# Meow.net
KiCad netlist of a schematic drawn in Altium Designer
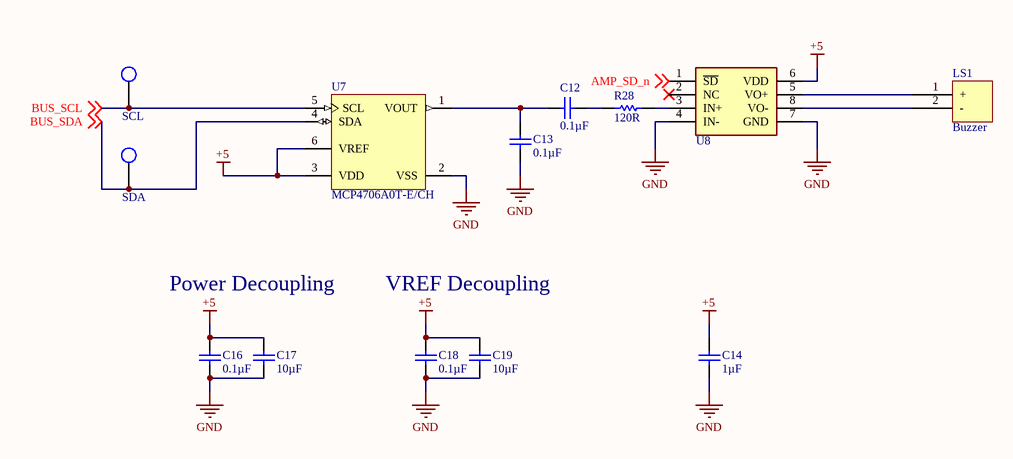
[diagram p0: Meow.SchDoc]

(export (version "E")
  (design (tool "Eeschema 10.0.6"))
  (components
    (comp (ref "C12")
      (value "Capacitor 0805")
      (footprint "Cap 0805")
      (description "Standard Capacitor")
      (fields (field (name "MANUFACTURER") "AVX") (field (name "CAPACITANCE") "0.1µF"))
      (libsource (lib "Standard Cap") (part "Capacitor 0805"))
    )
    (comp (ref "C13")
      (value "Capacitor 0805")
      (footprint "Cap 0805")
      (description "Standard Capacitor")
      (fields (field (name "MANUFACTURER") "AVX") (field (name "CAPACITANCE") "0.1µF"))
      (libsource (lib "Standard Cap") (part "Capacitor 0805"))
    )
    (comp (ref "C14")
      (value "Capacitor 0805")
      (footprint "Cap 0805")
      (description "Standard Capacitor")
      (fields (field (name "MANUFACTURER") "AVX") (field (name "CAPACITANCE") "1µF"))
      (libsource (lib "Standard Cap") (part "Capacitor 0805"))
    )
    (comp (ref "C16")
      (value "Capacitor 0805")
      (footprint "Cap 0805")
      (description "Standard Capacitor")
      (fields (field (name "MANUFACTURER") "AVX") (field (name "CAPACITANCE") "0.1µF"))
      (libsource (lib "Standard Cap") (part "Capacitor 0805"))
    )
    (comp (ref "C17")
      (value "Capacitor 0805")
      (footprint "Cap 0805")
      (description "Standard Capacitor")
      (fields (field (name "MANUFACTURER") "AVX") (field (name "CAPACITANCE") "10µF"))
      (libsource (lib "Standard Cap") (part "Capacitor 0805"))
    )
    (comp (ref "C18")
      (value "Capacitor 0805")
      (footprint "Cap 0805")
      (description "Standard Capacitor")
      (fields (field (name "MANUFACTURER") "AVX") (field (name "CAPACITANCE") "0.1µF"))
      (libsource (lib "Standard Cap") (part "Capacitor 0805"))
    )
    (comp (ref "C19")
      (value "Capacitor 0805")
      (footprint "Cap 0805")
      (description "Standard Capacitor")
      (fields (field (name "MANUFACTURER") "AVX") (field (name "CAPACITANCE") "10µF"))
      (libsource (lib "Standard Cap") (part "Capacitor 0805"))
    )
    (comp (ref "LS1")
      (value "Buzzer")
      (footprint "Buzzer")
      (description "PK-21N30PQ")
      (libsource (lib "Husky Robotics Standard Library 2019-2020") (part "Buzzer"))
    )
    (comp (ref "R28")
      (value "120R")
      (footprint "RESC0805(2012)_N")
      (description "Generic 0805 Resistor")
      (fields (field (name "TOLERANCE") "5 %") (field (name "POWER") "0.125 W"))
      (libsource (lib "Husky Robotics Standard Library 2019-2020") (part "Resistor 0805"))
    )
    (comp (ref "SCL")
      (value "Test Point")
      (footprint "Test Point Through-hole")
      (libsource (lib "Husky Robotics Standard Library 2019-2020") (part "Test Point"))
    )
    (comp (ref "SDA")
      (value "Test Point")
      (footprint "Test Point Through-hole")
      (libsource (lib "Husky Robotics Standard Library 2019-2020") (part "Test Point"))
    )
    (comp (ref "U7")
      (value "MCP4706A0T-E/CH")
      (footprint "SOT-23-CH6_M")
      (libsource (lib "Altium Content Vault") (part "CON-DAC-MCP4706-6"))
    )
    (comp (ref "U8")
      (value "Amplifier")
      (footprint "Amplifier")
      (description "PAM8302AADCR MEOW")
      (libsource (lib "Husky Robotics Standard Library 2019-2020") (part "Amplifier"))
    )
  )
  (nets
    (net (code "1") (name "+5") (class "Default")
      (node (ref "C14") (pin "2") (pinfunction "2_2") (pintype "passive"))
      (node (ref "C16") (pin "2") (pinfunction "2_2") (pintype "passive"))
      (node (ref "C17") (pin "1") (pinfunction "1_1") (pintype "passive"))
      (node (ref "C18") (pin "2") (pinfunction "2_2") (pintype "passive"))
      (node (ref "C19") (pin "2") (pinfunction "2_2") (pintype "passive"))
      (node (ref "U7") (pin "3") (pinfunction "VDD_3") (pintype "power_in"))
      (node (ref "U7") (pin "6") (pinfunction "VREF_6") (pintype "power_in"))
      (node (ref "U8") (pin "6") (pinfunction "VDD_6") (pintype "passive"))
    )
    (net (code "2") (name "AMP_SD_n") (class "Default")
      (node (ref "U8") (pin "1") (pinfunction "~{SD}_1") (pintype "passive"))
    )
    (net (code "3") (name "BUS_SCL") (class "Default")
      (node (ref "SCL") (pin "1") (pinfunction "1_1") (pintype "passive"))
      (node (ref "U7") (pin "5") (pinfunction "SCL_5") (pintype "input"))
    )
    (net (code "4") (name "BUS_SDA") (class "Default")
      (node (ref "SDA") (pin "1") (pinfunction "1_1") (pintype "passive"))
      (node (ref "U7") (pin "4") (pinfunction "SDA_4") (pintype "bidirectional"))
    )
    (net (code "5") (name "GND") (class "Default")
      (node (ref "C13") (pin "1") (pinfunction "1_1") (pintype "passive"))
      (node (ref "C14") (pin "1") (pinfunction "1_1") (pintype "passive"))
      (node (ref "C16") (pin "1") (pinfunction "1_1") (pintype "passive"))
      (node (ref "C17") (pin "2") (pinfunction "2_2") (pintype "passive"))
      (node (ref "C18") (pin "1") (pinfunction "1_1") (pintype "passive"))
      (node (ref "C19") (pin "1") (pinfunction "1_1") (pintype "passive"))
      (node (ref "U7") (pin "2") (pinfunction "VSS_2") (pintype "power_in"))
      (node (ref "U8") (pin "4") (pinfunction "IN-_4") (pintype "passive"))
      (node (ref "U8") (pin "7") (pinfunction "GND_7") (pintype "passive"))
    )
    (net (code "6") (name "Net-(C12-Pad2)") (class "Default")
      (node (ref "C12") (pin "2") (pinfunction "2_2") (pintype "passive"))
      (node (ref "R28") (pin "2") (pinfunction "2_2") (pintype "passive"))
    )
    (net (code "7") (name "Net-(LS1-+)") (class "Default")
      (node (ref "LS1") (pin "1") (pinfunction "+_1") (pintype "passive"))
      (node (ref "U8") (pin "5") (pinfunction "VO+_5") (pintype "passive"))
    )
    (net (code "8") (name "Net-(LS1--)") (class "Default")
      (node (ref "LS1") (pin "2") (pinfunction "-_2") (pintype "passive"))
      (node (ref "U8") (pin "8") (pinfunction "VO-_8") (pintype "passive"))
    )
    (net (code "9") (name "Net-(U7-VOUT)") (class "Default")
      (node (ref "C12") (pin "1") (pinfunction "1_1") (pintype "passive"))
      (node (ref "C13") (pin "2") (pinfunction "2_2") (pintype "passive"))
      (node (ref "U7") (pin "1") (pinfunction "VOUT_1") (pintype "output"))
    )
    (net (code "10") (name "Net-(U8-IN+)") (class "Default")
      (node (ref "R28") (pin "1") (pinfunction "1_1") (pintype "passive"))
      (node (ref "U8") (pin "3") (pinfunction "IN+_3") (pintype "passive"))
    )
    (net (code "11") (name "unconnected-(U8-NC-Pad2)") (class "Default")
      (node (ref "U8") (pin "2") (pinfunction "NC_2") (pintype "passive+no_connect"))
    )
  )
)
